# rfid_ctl3_v2.net
KiCad netlist of a schematic drawn in EAGLE
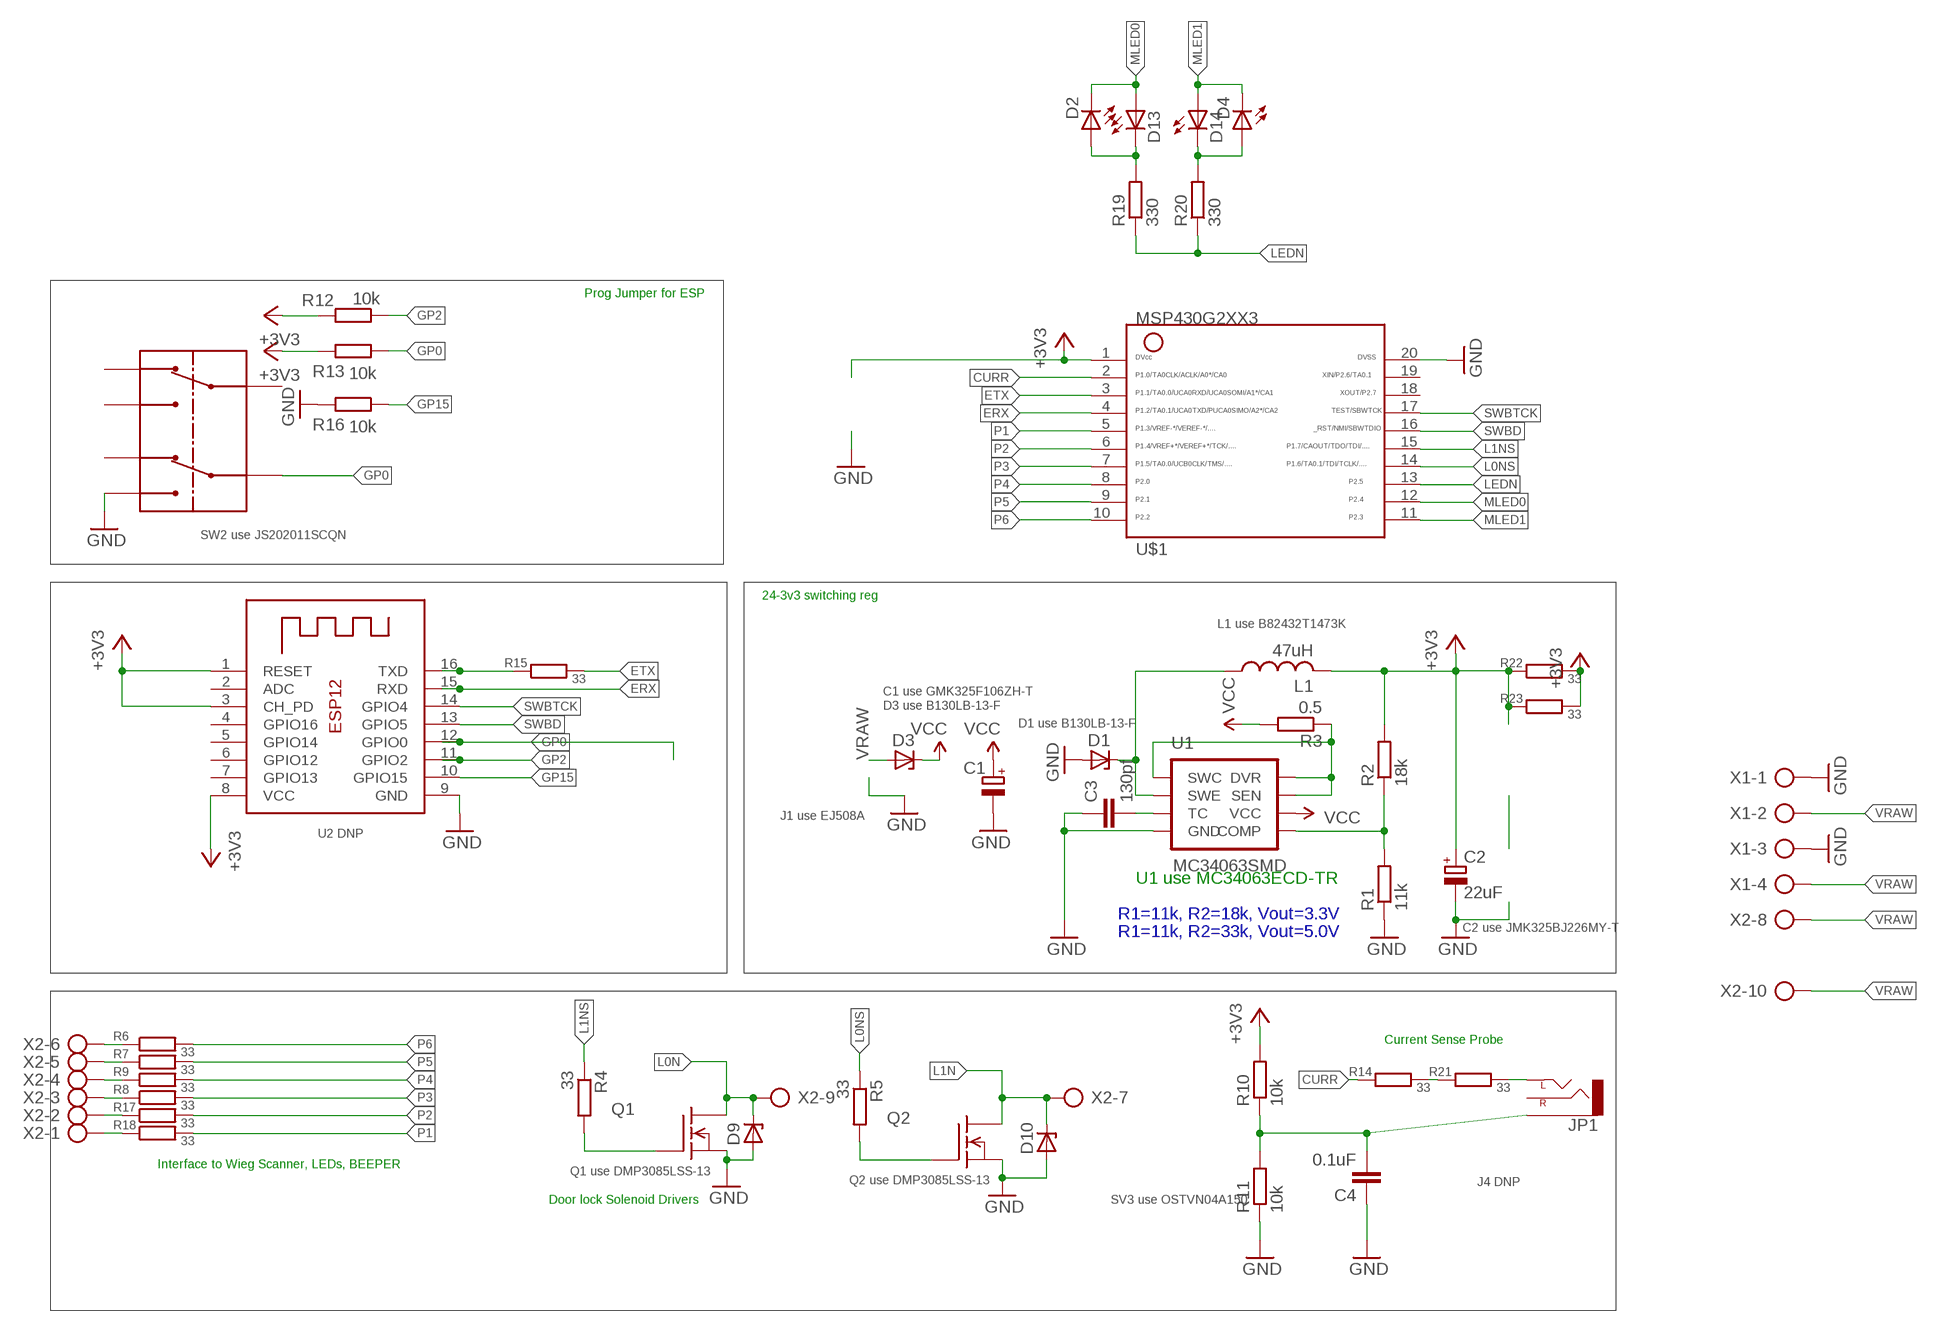
[diagram p0: schematic, sheet 1]

(export (version "E")
  (design (tool "Eeschema 10.0.6"))
  (components
    (comp (ref "C1")
      (value "CPOL-EUE2.5-7")
      (footprint "eagle-import:E2,5-7")
      (libsource (lib "eagle-import") (part "CPOL-EUE2.5-7"))
    )
    (comp (ref "C2")
      (value "22uF")
      (footprint "eagle-import:E2,5-7")
      (libsource (lib "eagle-import") (part "CPOL-EUE2.5-7"))
    )
    (comp (ref "C3")
      (value "130pf")
      (footprint "eagle-import:C1206")
      (libsource (lib "eagle-import") (part "C-EUC1206"))
    )
    (comp (ref "C4")
      (value "0.1uF")
      (footprint "eagle-import:C1206")
      (libsource (lib "eagle-import") (part "C-EUC1206"))
    )
    (comp (ref "D1")
      (value "ZENER-DIODESMB")
      (footprint "eagle-import:SMB")
      (libsource (lib "eagle-import") (part "ZENER-DIODESMB"))
    )
    (comp (ref "D2")
      (value "LED5MM")
      (footprint "eagle-import:LED5MM")
      (libsource (lib "eagle-import") (part "LED5MM"))
    )
    (comp (ref "D3")
      (value "ZENER-DIODESMB")
      (footprint "eagle-import:SMB")
      (libsource (lib "eagle-import") (part "ZENER-DIODESMB"))
    )
    (comp (ref "D4")
      (value "LED5MM")
      (footprint "eagle-import:LED5MM")
      (libsource (lib "eagle-import") (part "LED5MM"))
    )
    (comp (ref "D9")
      (value "ZENER-DIODESMB")
      (footprint "eagle-import:SMB")
      (libsource (lib "eagle-import") (part "ZENER-DIODESMB"))
    )
    (comp (ref "D10")
      (value "ZENER-DIODESMB")
      (footprint "eagle-import:SMB")
      (libsource (lib "eagle-import") (part "ZENER-DIODESMB"))
    )
    (comp (ref "D13")
      (value "LED5MM")
      (footprint "eagle-import:LED5MM")
      (libsource (lib "eagle-import") (part "LED5MM"))
    )
    (comp (ref "D14")
      (value "LED5MM")
      (footprint "eagle-import:LED5MM")
      (libsource (lib "eagle-import") (part "LED5MM"))
    )
    (comp (ref "JP1")
      (value "AUDIO-JACKSMD2")
      (footprint "eagle-import:AUDIO-JACK-3.5MM-SMD")
      (libsource (lib "eagle-import") (part "AUDIO-JACKSMD2"))
    )
    (comp (ref "L1")
      (value "47uH")
      (footprint "eagle-import:L1812")
      (libsource (lib "eagle-import") (part "L-USL1812"))
    )
    (comp (ref "Q1")
      (value "FDS5680")
      (footprint "eagle-import:SO-8")
      (libsource (lib "eagle-import") (part "FDS5680"))
    )
    (comp (ref "Q2")
      (value "FDS5680")
      (footprint "eagle-import:SO-8")
      (libsource (lib "eagle-import") (part "FDS5680"))
    )
    (comp (ref "R1")
      (value "11k")
      (footprint "eagle-import:R1206")
      (libsource (lib "eagle-import") (part "R-EU_R1206"))
    )
    (comp (ref "R2")
      (value "18k")
      (footprint "eagle-import:R1206")
      (libsource (lib "eagle-import") (part "R-EU_R1206"))
    )
    (comp (ref "R3")
      (value "0.5")
      (footprint "eagle-import:R1206")
      (libsource (lib "eagle-import") (part "R-EU_R1206"))
    )
    (comp (ref "R4")
      (value "33")
      (footprint "eagle-import:R1206")
      (libsource (lib "eagle-import") (part "R-EU_R1206"))
    )
    (comp (ref "R5")
      (value "33")
      (footprint "eagle-import:R1206")
      (libsource (lib "eagle-import") (part "R-EU_R1206"))
    )
    (comp (ref "R6")
      (value "33")
      (footprint "eagle-import:R1206")
      (libsource (lib "eagle-import") (part "R-EU_R1206"))
    )
    (comp (ref "R7")
      (value "33")
      (footprint "eagle-import:R1206")
      (libsource (lib "eagle-import") (part "R-EU_R1206"))
    )
    (comp (ref "R8")
      (value "33")
      (footprint "eagle-import:R1206")
      (libsource (lib "eagle-import") (part "R-EU_R1206"))
    )
    (comp (ref "R9")
      (value "33")
      (footprint "eagle-import:R1206")
      (libsource (lib "eagle-import") (part "R-EU_R1206"))
    )
    (comp (ref "R10")
      (value "10k")
      (footprint "eagle-import:R1206")
      (libsource (lib "eagle-import") (part "R-EU_R1206"))
    )
    (comp (ref "R11")
      (value "10k")
      (footprint "eagle-import:R1206")
      (libsource (lib "eagle-import") (part "R-EU_R1206"))
    )
    (comp (ref "R12")
      (value "10k")
      (footprint "eagle-import:R1206")
      (libsource (lib "eagle-import") (part "R-EU_R1206"))
    )
    (comp (ref "R13")
      (value "10k")
      (footprint "eagle-import:R1206")
      (libsource (lib "eagle-import") (part "R-EU_R1206"))
    )
    (comp (ref "R14")
      (value "33")
      (footprint "eagle-import:R1206")
      (libsource (lib "eagle-import") (part "R-EU_R1206"))
    )
    (comp (ref "R15")
      (value "33")
      (footprint "eagle-import:R1206")
      (libsource (lib "eagle-import") (part "R-EU_R1206"))
    )
    (comp (ref "R16")
      (value "10k")
      (footprint "eagle-import:R1206")
      (libsource (lib "eagle-import") (part "R-EU_R1206"))
    )
    (comp (ref "R17")
      (value "33")
      (footprint "eagle-import:R1206")
      (libsource (lib "eagle-import") (part "R-EU_R1206"))
    )
    (comp (ref "R18")
      (value "33")
      (footprint "eagle-import:R1206")
      (libsource (lib "eagle-import") (part "R-EU_R1206"))
    )
    (comp (ref "R19")
      (value "330")
      (footprint "eagle-import:R1206")
      (libsource (lib "eagle-import") (part "R-EU_R1206"))
    )
    (comp (ref "R20")
      (value "330")
      (footprint "eagle-import:R1206")
      (libsource (lib "eagle-import") (part "R-EU_R1206"))
    )
    (comp (ref "R21")
      (value "33")
      (footprint "eagle-import:R1206")
      (libsource (lib "eagle-import") (part "R-EU_R1206"))
    )
    (comp (ref "R22")
      (value "33")
      (footprint "eagle-import:R6332")
      (libsource (lib "eagle-import") (part "R-EU_R6332"))
    )
    (comp (ref "R23")
      (value "33")
      (footprint "eagle-import:R6332")
      (libsource (lib "eagle-import") (part "R-EU_R6332"))
    )
    (comp (ref "SW2")
      (value "L202011MS02Q")
      (footprint "eagle-import:SMT")
      (libsource (lib "eagle-import") (part "L202011MS02Q"))
    )
    (comp (ref "U$1")
      (value "G2XX3---N20")
      (footprint "eagle-import:N20")
      (libsource (lib "eagle-import") (part "G2XX3---N20"))
    )
    (comp (ref "U1")
      (value "MC34063SMD")
      (footprint "eagle-import:SO08")
      (libsource (lib "eagle-import") (part "MC34063SMD"))
    )
    (comp (ref "U2")
      (value "ESP-12")
      (footprint "eagle-import:ESP-12")
      (libsource (lib "eagle-import") (part "ESP-12"))
    )
    (comp (ref "X1")
      (value "AK300/4")
      (footprint "eagle-import:AK300_4")
      (libsource (lib "eagle-import") (part "AK300/4"))
    )
    (comp (ref "X2")
      (value "AK300/10")
      (footprint "eagle-import:AK300_10")
      (libsource (lib "eagle-import") (part "AK300/10"))
    )
  )
  (nets
    (net (code "1") (name "+3V3") (class "Default")
      (node (ref "C2") (pin "+") (pinfunction "+_+") (pintype "passive"))
      (node (ref "L1") (pin "2") (pinfunction "2_2") (pintype "passive"))
      (node (ref "R10") (pin "2") (pinfunction "2_2") (pintype "passive"))
      (node (ref "R12") (pin "2") (pinfunction "2_2") (pintype "passive"))
      (node (ref "R13") (pin "2") (pinfunction "2_2") (pintype "passive"))
      (node (ref "R2") (pin "2") (pinfunction "2_2") (pintype "passive"))
      (node (ref "R22") (pin "1") (pinfunction "1_1") (pintype "passive"))
      (node (ref "R22") (pin "2") (pinfunction "2_2") (pintype "passive"))
      (node (ref "R23") (pin "1") (pinfunction "1_1") (pintype "passive"))
      (node (ref "R23") (pin "2") (pinfunction "2_2") (pintype "passive"))
      (node (ref "U$1") (pin "1") (pinfunction "1_1") (pintype "bidirectional"))
      (node (ref "U2") (pin "1") (pinfunction "RESET_1") (pintype "input"))
      (node (ref "U2") (pin "3") (pinfunction "CH_PD_3") (pintype "input"))
      (node (ref "U2") (pin "8") (pinfunction "VCC_8") (pintype "power_in"))
    )
    (net (code "2") (name "CURR") (class "Default")
      (node (ref "R14") (pin "1") (pinfunction "1_1") (pintype "passive"))
      (node (ref "U$1") (pin "2") (pinfunction "2_2") (pintype "bidirectional"))
    )
    (net (code "3") (name "ERX") (class "Default")
      (node (ref "U$1") (pin "4") (pinfunction "4_4") (pintype "bidirectional"))
      (node (ref "U2") (pin "15") (pinfunction "RXD_15") (pintype "input"))
    )
    (net (code "4") (name "ETX") (class "Default")
      (node (ref "R15") (pin "2") (pinfunction "2_2") (pintype "passive"))
      (node (ref "U$1") (pin "3") (pinfunction "3_3") (pintype "bidirectional"))
    )
    (net (code "5") (name "GND") (class "Default")
      (node (ref "C1") (pin "-") (pinfunction "-_-") (pintype "passive"))
      (node (ref "C2") (pin "-") (pinfunction "-_-") (pintype "passive"))
      (node (ref "C3") (pin "1") (pinfunction "1_1") (pintype "passive"))
      (node (ref "C4") (pin "1") (pinfunction "1_1") (pintype "passive"))
      (node (ref "D1") (pin "A") (pinfunction "A_A") (pintype "passive"))
      (node (ref "D10") (pin "A") (pinfunction "A_A") (pintype "passive"))
      (node (ref "D9") (pin "A") (pinfunction "A_A") (pintype "passive"))
      (node (ref "Q1") (pin "1") (pinfunction "S_1") (pintype "passive"))
      (node (ref "Q1") (pin "2") (pinfunction "S_2") (pintype "passive"))
      (node (ref "Q1") (pin "3") (pinfunction "S_3") (pintype "passive"))
      (node (ref "Q2") (pin "1") (pinfunction "S_1") (pintype "passive"))
      (node (ref "Q2") (pin "2") (pinfunction "S_2") (pintype "passive"))
      (node (ref "Q2") (pin "3") (pinfunction "S_3") (pintype "passive"))
      (node (ref "R1") (pin "1") (pinfunction "1_1") (pintype "passive"))
      (node (ref "R11") (pin "1") (pinfunction "1_1") (pintype "passive"))
      (node (ref "R16") (pin "2") (pinfunction "2_2") (pintype "passive"))
      (node (ref "SW2") (pin "B1") (pinfunction "B1_B1") (pintype "bidirectional"))
      (node (ref "U$1") (pin "20") (pinfunction "20_20") (pintype "bidirectional"))
      (node (ref "U1") (pin "4") (pinfunction "GND_4") (pintype "bidirectional"))
      (node (ref "U2") (pin "9") (pinfunction "GND_9") (pintype "power_in"))
      (node (ref "X1") (pin "1") (pinfunction "KL_1") (pintype "passive"))
      (node (ref "X1") (pin "3") (pinfunction "KL_3") (pintype "passive"))
    )
    (net (code "6") (name "GP0") (class "Default")
      (node (ref "R13") (pin "1") (pinfunction "1_1") (pintype "passive"))
      (node (ref "SW2") (pin "B") (pinfunction "B_B") (pintype "bidirectional"))
      (node (ref "U2") (pin "12") (pinfunction "GPIO0_12") (pintype "bidirectional"))
    )
    (net (code "7") (name "GP2") (class "Default")
      (node (ref "R12") (pin "1") (pinfunction "1_1") (pintype "passive"))
      (node (ref "U2") (pin "11") (pinfunction "GPIO2_11") (pintype "bidirectional"))
    )
    (net (code "8") (name "GP15") (class "Default")
      (node (ref "R16") (pin "1") (pinfunction "1_1") (pintype "passive"))
      (node (ref "U2") (pin "10") (pinfunction "GPIO15_10") (pintype "bidirectional"))
    )
    (net (code "9") (name "L0N") (class "Default")
      (node (ref "D9") (pin "C") (pinfunction "C_C") (pintype "passive"))
      (node (ref "Q1") (pin "5") (pinfunction "D_5") (pintype "passive"))
      (node (ref "Q1") (pin "6") (pinfunction "D_6") (pintype "passive"))
      (node (ref "Q1") (pin "7") (pinfunction "D_7") (pintype "passive"))
      (node (ref "Q1") (pin "8") (pinfunction "D_8") (pintype "passive"))
      (node (ref "X2") (pin "9") (pinfunction "KL_9") (pintype "passive"))
    )
    (net (code "10") (name "L0NS") (class "Default")
      (node (ref "R5") (pin "1") (pinfunction "1_1") (pintype "passive"))
      (node (ref "U$1") (pin "14") (pinfunction "14_14") (pintype "bidirectional"))
    )
    (net (code "11") (name "L1N") (class "Default")
      (node (ref "D10") (pin "C") (pinfunction "C_C") (pintype "passive"))
      (node (ref "Q2") (pin "5") (pinfunction "D_5") (pintype "passive"))
      (node (ref "Q2") (pin "6") (pinfunction "D_6") (pintype "passive"))
      (node (ref "Q2") (pin "7") (pinfunction "D_7") (pintype "passive"))
      (node (ref "Q2") (pin "8") (pinfunction "D_8") (pintype "passive"))
      (node (ref "X2") (pin "7") (pinfunction "KL_7") (pintype "passive"))
    )
    (net (code "12") (name "L1NS") (class "Default")
      (node (ref "R4") (pin "1") (pinfunction "1_1") (pintype "passive"))
      (node (ref "U$1") (pin "15") (pinfunction "15_15") (pintype "bidirectional"))
    )
    (net (code "13") (name "LEDN") (class "Default")
      (node (ref "R19") (pin "1") (pinfunction "1_1") (pintype "passive"))
      (node (ref "R20") (pin "1") (pinfunction "1_1") (pintype "passive"))
      (node (ref "U$1") (pin "13") (pinfunction "13_13") (pintype "bidirectional"))
    )
    (net (code "14") (name "MLED0") (class "Default")
      (node (ref "D13") (pin "A") (pinfunction "A_A") (pintype "passive"))
      (node (ref "D2") (pin "K") (pinfunction "C_K") (pintype "passive"))
      (node (ref "U$1") (pin "12") (pinfunction "12_12") (pintype "bidirectional"))
    )
    (net (code "15") (name "MLED1") (class "Default")
      (node (ref "D14") (pin "A") (pinfunction "A_A") (pintype "passive"))
      (node (ref "D4") (pin "K") (pinfunction "C_K") (pintype "passive"))
      (node (ref "U$1") (pin "11") (pinfunction "11_11") (pintype "bidirectional"))
    )
    (net (code "16") (name "Net-(C4-Pad2)") (class "Default")
      (node (ref "C4") (pin "2") (pinfunction "2_2") (pintype "passive"))
      (node (ref "JP1") (pin "SLEEVE") (pinfunction "SLEEVE_SLEEVE") (pintype "bidirectional"))
      (node (ref "R10") (pin "1") (pinfunction "1_1") (pintype "passive"))
      (node (ref "R11") (pin "2") (pinfunction "2_2") (pintype "passive"))
    )
    (net (code "17") (name "Net-(D13-C)") (class "Default")
      (node (ref "D13") (pin "K") (pinfunction "C_K") (pintype "passive"))
      (node (ref "D2") (pin "A") (pinfunction "A_A") (pintype "passive"))
      (node (ref "R19") (pin "2") (pinfunction "2_2") (pintype "passive"))
    )
    (net (code "18") (name "Net-(D14-C)") (class "Default")
      (node (ref "D14") (pin "K") (pinfunction "C_K") (pintype "passive"))
      (node (ref "D4") (pin "A") (pinfunction "A_A") (pintype "passive"))
      (node (ref "R20") (pin "2") (pinfunction "2_2") (pintype "passive"))
    )
    (net (code "19") (name "Net-(JP1-LEFT)") (class "Default")
      (node (ref "JP1") (pin "TIP") (pinfunction "LEFT_TIP") (pintype "bidirectional"))
      (node (ref "R21") (pin "2") (pinfunction "2_2") (pintype "passive"))
    )
    (net (code "20") (name "Net-(Q1-G)") (class "Default")
      (node (ref "Q1") (pin "4") (pinfunction "G_4") (pintype "passive"))
      (node (ref "R4") (pin "2") (pinfunction "2_2") (pintype "passive"))
    )
    (net (code "21") (name "Net-(Q2-G)") (class "Default")
      (node (ref "Q2") (pin "4") (pinfunction "G_4") (pintype "passive"))
      (node (ref "R5") (pin "2") (pinfunction "2_2") (pintype "passive"))
    )
    (net (code "22") (name "Net-(R14-Pad2)") (class "Default")
      (node (ref "R14") (pin "2") (pinfunction "2_2") (pintype "passive"))
      (node (ref "R21") (pin "1") (pinfunction "1_1") (pintype "passive"))
    )
    (net (code "23") (name "Net-(U1-COMP)") (class "Default")
      (node (ref "R1") (pin "2") (pinfunction "2_2") (pintype "passive"))
      (node (ref "R2") (pin "1") (pinfunction "1_1") (pintype "passive"))
      (node (ref "U1") (pin "5") (pinfunction "COMP_5") (pintype "bidirectional"))
    )
    (net (code "24") (name "Net-(U1-DVR)") (class "Default")
      (node (ref "R3") (pin "1") (pinfunction "1_1") (pintype "passive"))
      (node (ref "U1") (pin "1") (pinfunction "SWC_1") (pintype "bidirectional"))
      (node (ref "U1") (pin "7") (pinfunction "SEN_7") (pintype "bidirectional"))
      (node (ref "U1") (pin "8") (pinfunction "DVR_8") (pintype "bidirectional"))
    )
    (net (code "25") (name "Net-(U1-SWE)") (class "Default")
      (node (ref "D1") (pin "C") (pinfunction "C_C") (pintype "passive"))
      (node (ref "L1") (pin "1") (pinfunction "1_1") (pintype "passive"))
      (node (ref "U1") (pin "2") (pinfunction "SWE_2") (pintype "bidirectional"))
    )
    (net (code "26") (name "Net-(U1-TC)") (class "Default")
      (node (ref "C3") (pin "2") (pinfunction "2_2") (pintype "passive"))
      (node (ref "U1") (pin "3") (pinfunction "TC_3") (pintype "bidirectional"))
    )
    (net (code "27") (name "Net-(U2-TXD)") (class "Default")
      (node (ref "R15") (pin "1") (pinfunction "1_1") (pintype "passive"))
      (node (ref "U2") (pin "16") (pinfunction "TXD_16") (pintype "output"))
    )
    (net (code "28") (name "Net-(X2A-KL)") (class "Default")
      (node (ref "R18") (pin "1") (pinfunction "1_1") (pintype "passive"))
      (node (ref "X2") (pin "1") (pinfunction "KL_1") (pintype "passive"))
    )
    (net (code "29") (name "Net-(X2C-KL)") (class "Default")
      (node (ref "R17") (pin "1") (pinfunction "1_1") (pintype "passive"))
      (node (ref "X2") (pin "2") (pinfunction "KL_2") (pintype "passive"))
    )
    (net (code "30") (name "Net-(X2D-KL)") (class "Default")
      (node (ref "R9") (pin "1") (pinfunction "1_1") (pintype "passive"))
      (node (ref "X2") (pin "3") (pinfunction "KL_3") (pintype "passive"))
    )
    (net (code "31") (name "Net-(X2E-KL)") (class "Default")
      (node (ref "R8") (pin "1") (pinfunction "1_1") (pintype "passive"))
      (node (ref "X2") (pin "4") (pinfunction "KL_4") (pintype "passive"))
    )
    (net (code "32") (name "Net-(X2F-KL)") (class "Default")
      (node (ref "R7") (pin "1") (pinfunction "1_1") (pintype "passive"))
      (node (ref "X2") (pin "5") (pinfunction "KL_5") (pintype "passive"))
    )
    (net (code "33") (name "Net-(X2G-KL)") (class "Default")
      (node (ref "R6") (pin "1") (pinfunction "1_1") (pintype "passive"))
      (node (ref "X2") (pin "6") (pinfunction "KL_6") (pintype "passive"))
    )
    (net (code "34") (name "P1") (class "Default")
      (node (ref "R18") (pin "2") (pinfunction "2_2") (pintype "passive"))
      (node (ref "U$1") (pin "5") (pinfunction "5_5") (pintype "bidirectional"))
    )
    (net (code "35") (name "P2") (class "Default")
      (node (ref "R17") (pin "2") (pinfunction "2_2") (pintype "passive"))
      (node (ref "U$1") (pin "6") (pinfunction "6_6") (pintype "bidirectional"))
    )
    (net (code "36") (name "P3") (class "Default")
      (node (ref "R9") (pin "2") (pinfunction "2_2") (pintype "passive"))
      (node (ref "U$1") (pin "7") (pinfunction "7_7") (pintype "bidirectional"))
    )
    (net (code "37") (name "P4") (class "Default")
      (node (ref "R8") (pin "2") (pinfunction "2_2") (pintype "passive"))
      (node (ref "U$1") (pin "8") (pinfunction "8_8") (pintype "bidirectional"))
    )
    (net (code "38") (name "P5") (class "Default")
      (node (ref "R7") (pin "2") (pinfunction "2_2") (pintype "passive"))
      (node (ref "U$1") (pin "9") (pinfunction "9_9") (pintype "bidirectional"))
    )
    (net (code "39") (name "P6") (class "Default")
      (node (ref "R6") (pin "2") (pinfunction "2_2") (pintype "passive"))
      (node (ref "U$1") (pin "10") (pinfunction "10_10") (pintype "bidirectional"))
    )
    (net (code "40") (name "SWBD") (class "Default")
      (node (ref "U$1") (pin "16") (pinfunction "16_16") (pintype "bidirectional"))
      (node (ref "U2") (pin "13") (pinfunction "GPIO5_13") (pintype "bidirectional"))
    )
    (net (code "41") (name "SWBTCK") (class "Default")
      (node (ref "U$1") (pin "17") (pinfunction "17_17") (pintype "bidirectional"))
      (node (ref "U2") (pin "14") (pinfunction "GPIO4_14") (pintype "bidirectional"))
    )
    (net (code "42") (name "VCC") (class "Default")
      (node (ref "C1") (pin "+") (pinfunction "+_+") (pintype "passive"))
      (node (ref "D3") (pin "C") (pinfunction "C_C") (pintype "passive"))
      (node (ref "R3") (pin "2") (pinfunction "2_2") (pintype "passive"))
      (node (ref "U1") (pin "6") (pinfunction "VCC_6") (pintype "bidirectional"))
    )
    (net (code "43") (name "VRAW") (class "Default")
      (node (ref "D3") (pin "A") (pinfunction "A_A") (pintype "passive"))
      (node (ref "X1") (pin "2") (pinfunction "KL_2") (pintype "passive"))
      (node (ref "X1") (pin "4") (pinfunction "KL_4") (pintype "passive"))
      (node (ref "X2") (pin "10") (pinfunction "KL_10") (pintype "passive"))
      (node (ref "X2") (pin "8") (pinfunction "KL_8") (pintype "passive"))
    )
    (net (code "44") (name "unconnected-(JP1-RIGHT-PadRING)") (class "Default")
      (node (ref "JP1") (pin "RING") (pinfunction "RIGHT_RING") (pintype "bidirectional"))
    )
    (net (code "45") (name "unconnected-(SW2-PadA)") (class "Default")
      (node (ref "SW2") (pin "A") (pinfunction "A_A") (pintype "bidirectional"))
    )
    (net (code "46") (name "unconnected-(SW2-PadA1)") (class "Default")
      (node (ref "SW2") (pin "A1") (pinfunction "A1_A1") (pintype "bidirectional"))
    )
    (net (code "47") (name "unconnected-(SW2-PadA2)") (class "Default")
      (node (ref "SW2") (pin "A2") (pinfunction "A2_A2") (pintype "bidirectional"))
    )
    (net (code "48") (name "unconnected-(SW2-PadB2)") (class "Default")
      (node (ref "SW2") (pin "B2") (pinfunction "B2_B2") (pintype "bidirectional"))
    )
    (net (code "49") (name "unconnected-(U$1-Pad18)") (class "Default")
      (node (ref "U$1") (pin "18") (pinfunction "18_18") (pintype "bidirectional"))
    )
    (net (code "50") (name "unconnected-(U$1-Pad19)") (class "Default")
      (node (ref "U$1") (pin "19") (pinfunction "19_19") (pintype "bidirectional"))
    )
    (net (code "51") (name "unconnected-(U2-ADC-Pad2)") (class "Default")
      (node (ref "U2") (pin "2") (pinfunction "ADC_2") (pintype "passive"))
    )
    (net (code "52") (name "unconnected-(U2-GPIO12-Pad6)") (class "Default")
      (node (ref "U2") (pin "6") (pinfunction "GPIO12_6") (pintype "bidirectional"))
    )
    (net (code "53") (name "unconnected-(U2-GPIO13-Pad7)") (class "Default")
      (node (ref "U2") (pin "7") (pinfunction "GPIO13_7") (pintype "bidirectional"))
    )
    (net (code "54") (name "unconnected-(U2-GPIO14-Pad5)") (class "Default")
      (node (ref "U2") (pin "5") (pinfunction "GPIO14_5") (pintype "bidirectional"))
    )
    (net (code "55") (name "unconnected-(U2-GPIO16-Pad4)") (class "Default")
      (node (ref "U2") (pin "4") (pinfunction "GPIO16_4") (pintype "bidirectional"))
    )
  )
)
